# Arduino_extension_connectors.net
KiCad netlist of a schematic drawn in Altium Designer
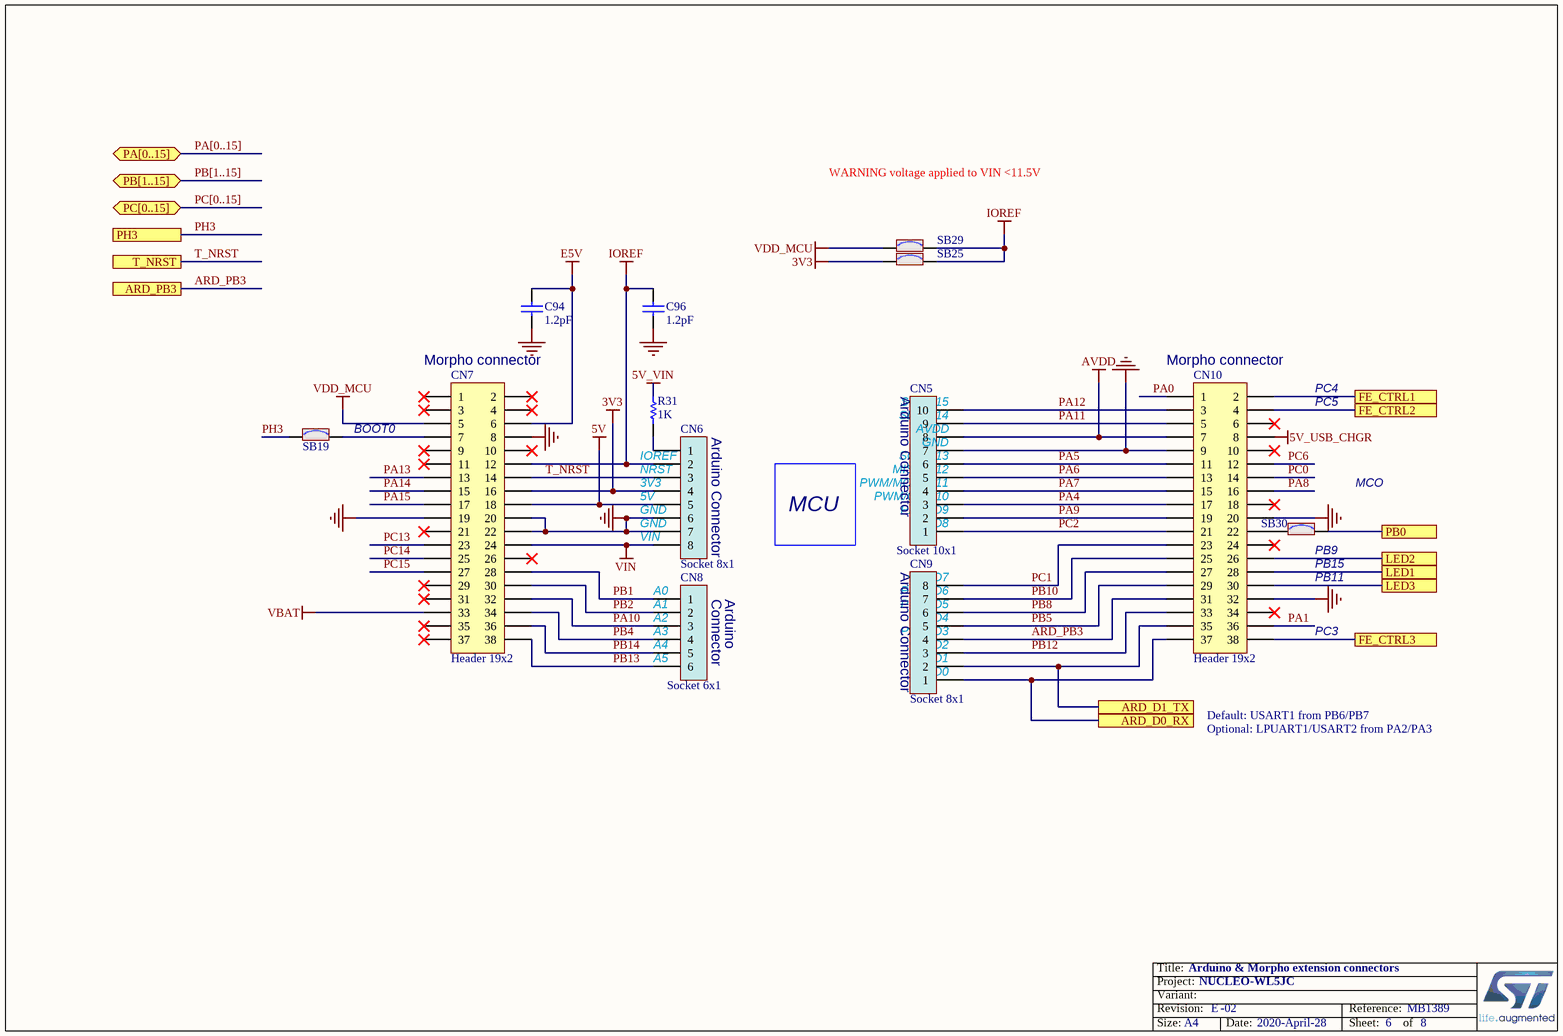
[diagram p0: Arduino_extension_connectors.SchDoc]

(export (version "E")
  (design (tool "Eeschema 10.0.6"))
  (components
    (comp (ref "C94")
      (value "1.2pF")
      (footprint "C0402")
      (description "Capacitor, High Q type for high frequency and high power, SMD, 1.2pF, 50V, 0,05pf, 0402")
      (fields (field (name "INTERNAL_PART_NUMBER") "MCD-02065") (field (name "MANUFACTURER") "MURATA"))
      (libsource (lib "MCD_PARTS_database") (part "Capacitor"))
    )
    (comp (ref "C96")
      (value "1.2pF")
      (footprint "C0402")
      (description "Capacitor, High Q type for high frequency and high power, SMD, 1.2pF, 50V, 0,05pf, 0402")
      (fields (field (name "INTERNAL_PART_NUMBER") "MCD-02065") (field (name "MANUFACTURER") "MURATA"))
      (libsource (lib "MCD_PARTS_database") (part "Capacitor"))
    )
    (comp (ref "CN5")
      (value "Socket 10x1")
      (footprint "CON_SAMTEC_SSW-110-03-X-S")
      (description "Socket, 10x1, 2.54mm, VR, TH, Height 8.51mm/10mm")
      (fields
        (field (name "INTERNAL_PART_NUMBER") "MCD-00262")
        (field (name "MANUFACTURER_PART_NUMBER") "SSW-110-03-x-S")
        (field (name "PROVIDED_BY") "SUBCO")
      )
      (libsource (lib "MCD_PARTS_database") (part "Socket 10x1"))
    )
    (comp (ref "CN6")
      (value "Socket 8x1")
      (footprint "CON_SAMTEC_SSW-108-03-X-S")
      (description "Socket, 8x1, 2.54mm, VR, TH, Height 8.51mm/10mm")
      (fields
        (field (name "INTERNAL_PART_NUMBER") "MCD-00261")
        (field (name "MANUFACTURER_PART_NUMBER") "SSW-108-03-x-S")
        (field (name "PROVIDED_BY") "SUBCO")
      )
      (libsource (lib "MCD_PARTS_database") (part "Socket 8x1"))
    )
    (comp (ref "CN7")
      (value "Header 19x2")
      (footprint "CON_SAMTEC_TSW-119-09-X-D")
      (description "Header, 19x2, 2,54mm, VR, TH, Height 5.84mm/10.16mm")
      (fields
        (field (name "INTERNAL_PART_NUMBER") "MCD-00213")
        (field (name "MANUFACTURER_PART_NUMBER") "TSW-119-09-x-D")
        (field (name "PROVIDED_BY") "SUBCO")
      )
      (libsource (lib "MCD_PARTS_database") (part "Header 19x2"))
    )
    (comp (ref "CN8")
      (value "Socket 6x1")
      (footprint "CON_SAMTEC_SSW-106-03-X-S")
      (description "Socket, 6x1, 2.54mm, VR, TH, Height 8.51mm/10mm")
      (fields
        (field (name "INTERNAL_PART_NUMBER") "MCD-00260")
        (field (name "MANUFACTURER_PART_NUMBER") "SSW-106-03-x-S")
        (field (name "PROVIDED_BY") "SUBCO")
      )
      (libsource (lib "MCD_PARTS_database") (part "Socket 6x1"))
    )
    (comp (ref "CN9")
      (value "Socket 8x1")
      (footprint "CON_SAMTEC_SSW-108-03-X-S")
      (description "Socket, 8x1, 2.54mm, VR, TH, Height 8.51mm/10mm")
      (fields
        (field (name "INTERNAL_PART_NUMBER") "MCD-00261")
        (field (name "MANUFACTURER_PART_NUMBER") "SSW-108-03-x-S")
        (field (name "PROVIDED_BY") "SUBCO")
      )
      (libsource (lib "") (part "Socket 8x1_1"))
    )
    (comp (ref "CN10")
      (value "Header 19x2")
      (footprint "CON_SAMTEC_TSW-119-09-X-D")
      (description "Header, 19x2, 2,54mm, VR, TH, Height 5.84mm/10.16mm")
      (fields
        (field (name "INTERNAL_PART_NUMBER") "MCD-00213")
        (field (name "MANUFACTURER_PART_NUMBER") "TSW-119-09-x-D")
        (field (name "PROVIDED_BY") "SUBCO")
      )
      (libsource (lib "MCD_PARTS_database") (part "Header 19x2"))
    )
    (comp (ref "R31")
      (value "1K")
      (footprint "R0603")
      (description "Resistor,1K,0603,1%,1/10W")
      (fields
        (field (name "INTERNAL_PART_NUMBER") "MCD-00070")
        (field (name "MANUFACTURER_PART_NUMBER") "RC0603FR-071KL")
        (field (name "PROVIDED_BY") "SUBCO")
      )
      (libsource (lib "MCD_PARTS_database") (part "Resistor"))
    )
    (comp (ref "SB19")
      (value "~")
      (footprint "SOLDER-BRIDGE_R0603-0R")
      (description "Solder Bridge ON")
      (fields
        (field (name "INTERNAL_PART_NUMBER") "MCD-00071")
        (field (name "MANUFACTURER_PART_NUMBER") "RC0603JR-070RL")
        (field (name "PROVIDED_BY") "SUBCO")
      )
      (libsource (lib "MCD_PARTS_database") (part "SB_ON"))
    )
    (comp (ref "SB25")
      (value "~")
      (footprint "SOLDER-BRIDGE_R0603-0R")
      (description "Solder Bridge ON")
      (fields
        (field (name "INTERNAL_PART_NUMBER") "MCD-00071")
        (field (name "MANUFACTURER_PART_NUMBER") "RC0603JR-070RL")
        (field (name "PROVIDED_BY") "SUBCO")
      )
      (libsource (lib "MCD_PARTS_database") (part "SB_ON"))
    )
    (comp (ref "SB29")
      (value "~")
      (footprint "SOLDER-BRIDGE_R0603-0R")
      (description "Solder Bridge ON")
      (fields
        (field (name "INTERNAL_PART_NUMBER") "MCD-00071")
        (field (name "MANUFACTURER_PART_NUMBER") "RC0603JR-070RL")
        (field (name "PROVIDED_BY") "SUBCO")
      )
      (libsource (lib "MCD_PARTS_database") (part "SB_ON"))
    )
    (comp (ref "SB30")
      (value "~")
      (footprint "SOLDER-BRIDGE_R0603-0R")
      (description "Solder Bridge ON")
      (fields
        (field (name "INTERNAL_PART_NUMBER") "MCD-00071")
        (field (name "MANUFACTURER_PART_NUMBER") "RC0603JR-070RL")
        (field (name "PROVIDED_BY") "SUBCO")
      )
      (libsource (lib "MCD_PARTS_database") (part "SB_ON"))
    )
  )
  (nets
    (net (code "18") (name "/ARD_D0_RX") (class "Default")
      (node (ref "CN10") (pin "37") (pinfunction "37_37") (pintype "passive"))
      (node (ref "CN9") (pin "1") (pinfunction "1_1") (pintype "passive"))
    )
    (net (code "19") (name "/ARD_D1_TX") (class "Default")
      (node (ref "CN10") (pin "35") (pinfunction "35_35") (pintype "passive"))
      (node (ref "CN9") (pin "2") (pinfunction "2_2") (pintype "passive"))
    )
    (net (code "20") (name "/ARD_PB3") (class "Default")
      (node (ref "CN10") (pin "31") (pinfunction "31_31") (pintype "passive"))
      (node (ref "CN9") (pin "4") (pinfunction "4_4") (pintype "passive"))
    )
    (net (code "21") (name "/FE_CTRL1") (class "Default")
      (node (ref "CN10") (pin "2") (pinfunction "2_2") (pintype "passive"))
    )
    (net (code "22") (name "/FE_CTRL2") (class "Default")
      (node (ref "CN10") (pin "4") (pinfunction "4_4") (pintype "passive"))
    )
    (net (code "23") (name "/FE_CTRL3") (class "Default")
      (node (ref "CN10") (pin "38") (pinfunction "38_38") (pintype "passive"))
    )
    (net (code "24") (name "/LED1") (class "Default")
      (node (ref "CN10") (pin "28") (pinfunction "28_28") (pintype "passive"))
    )
    (net (code "25") (name "/LED2") (class "Default")
      (node (ref "CN10") (pin "26") (pinfunction "26_26") (pintype "passive"))
    )
    (net (code "26") (name "/LED3") (class "Default")
      (node (ref "CN10") (pin "30") (pinfunction "30_30") (pintype "passive"))
    )
    (net (code "27") (name "/PA0") (class "Default")
      (node (ref "CN10") (pin "1") (pinfunction "1_1") (pintype "passive"))
    )
    (net (code "28") (name "/PA1") (class "Default")
      (node (ref "CN10") (pin "36") (pinfunction "36_36") (pintype "passive"))
    )
    (net (code "29") (name "/PA4") (class "Default")
      (node (ref "CN10") (pin "17") (pinfunction "17_17") (pintype "passive"))
      (node (ref "CN5") (pin "3") (pinfunction "3_3") (pintype "passive"))
    )
    (net (code "30") (name "/PA5") (class "Default")
      (node (ref "CN10") (pin "11") (pinfunction "11_11") (pintype "passive"))
      (node (ref "CN5") (pin "6") (pinfunction "6_6") (pintype "passive"))
    )
    (net (code "31") (name "/PA6") (class "Default")
      (node (ref "CN10") (pin "13") (pinfunction "13_13") (pintype "passive"))
      (node (ref "CN5") (pin "5") (pinfunction "5_5") (pintype "passive"))
    )
    (net (code "32") (name "/PA7") (class "Default")
      (node (ref "CN10") (pin "15") (pinfunction "15_15") (pintype "passive"))
      (node (ref "CN5") (pin "4") (pinfunction "4_4") (pintype "passive"))
    )
    (net (code "33") (name "/PA8") (class "Default")
      (node (ref "CN10") (pin "16") (pinfunction "16_16") (pintype "passive"))
    )
    (net (code "34") (name "/PA9") (class "Default")
      (node (ref "CN10") (pin "19") (pinfunction "19_19") (pintype "passive"))
      (node (ref "CN5") (pin "2") (pinfunction "2_2") (pintype "passive"))
    )
    (net (code "35") (name "/PA10") (class "Default")
      (node (ref "CN7") (pin "32") (pinfunction "32_32") (pintype "passive"))
      (node (ref "CN8") (pin "3") (pinfunction "3_3") (pintype "passive"))
    )
    (net (code "36") (name "/PA11") (class "Default")
      (node (ref "CN10") (pin "5") (pinfunction "5_5") (pintype "passive"))
      (node (ref "CN5") (pin "9") (pinfunction "9_9") (pintype "passive"))
    )
    (net (code "37") (name "/PA12") (class "Default")
      (node (ref "CN10") (pin "3") (pinfunction "3_3") (pintype "passive"))
      (node (ref "CN5") (pin "10") (pinfunction "10_10") (pintype "passive"))
    )
    (net (code "38") (name "/PA13") (class "Default")
      (node (ref "CN7") (pin "13") (pinfunction "13_13") (pintype "passive"))
    )
    (net (code "39") (name "/PA14") (class "Default")
      (node (ref "CN7") (pin "15") (pinfunction "15_15") (pintype "passive"))
    )
    (net (code "40") (name "/PA15") (class "Default")
      (node (ref "CN7") (pin "17") (pinfunction "17_17") (pintype "passive"))
    )
    (net (code "42") (name "/PB0") (class "Default")
      (node (ref "SB30") (pin "2") (pinfunction "2_2") (pintype "passive"))
    )
    (net (code "43") (name "/PB1") (class "Default")
      (node (ref "CN7") (pin "28") (pinfunction "28_28") (pintype "passive"))
      (node (ref "CN8") (pin "1") (pinfunction "1_1") (pintype "passive"))
    )
    (net (code "44") (name "/PB2") (class "Default")
      (node (ref "CN7") (pin "30") (pinfunction "30_30") (pintype "passive"))
      (node (ref "CN8") (pin "2") (pinfunction "2_2") (pintype "passive"))
    )
    (net (code "45") (name "/PB4") (class "Default")
      (node (ref "CN7") (pin "34") (pinfunction "34_34") (pintype "passive"))
      (node (ref "CN8") (pin "4") (pinfunction "4_4") (pintype "passive"))
    )
    (net (code "46") (name "/PB5") (class "Default")
      (node (ref "CN10") (pin "29") (pinfunction "29_29") (pintype "passive"))
      (node (ref "CN9") (pin "5") (pinfunction "5_5") (pintype "passive"))
    )
    (net (code "47") (name "/PB8") (class "Default")
      (node (ref "CN10") (pin "27") (pinfunction "27_27") (pintype "passive"))
      (node (ref "CN9") (pin "6") (pinfunction "6_6") (pintype "passive"))
    )
    (net (code "48") (name "/PB10") (class "Default")
      (node (ref "CN10") (pin "25") (pinfunction "25_25") (pintype "passive"))
      (node (ref "CN9") (pin "7") (pinfunction "7_7") (pintype "passive"))
    )
    (net (code "49") (name "/PB12") (class "Default")
      (node (ref "CN10") (pin "33") (pinfunction "33_33") (pintype "passive"))
      (node (ref "CN9") (pin "3") (pinfunction "3_3") (pintype "passive"))
    )
    (net (code "50") (name "/PB13") (class "Default")
      (node (ref "CN7") (pin "38") (pinfunction "38_38") (pintype "passive"))
      (node (ref "CN8") (pin "6") (pinfunction "6_6") (pintype "passive"))
    )
    (net (code "51") (name "/PB14") (class "Default")
      (node (ref "CN7") (pin "36") (pinfunction "36_36") (pintype "passive"))
      (node (ref "CN8") (pin "5") (pinfunction "5_5") (pintype "passive"))
    )
    (net (code "53") (name "/PC0") (class "Default")
      (node (ref "CN10") (pin "14") (pinfunction "14_14") (pintype "passive"))
    )
    (net (code "54") (name "/PC1") (class "Default")
      (node (ref "CN10") (pin "23") (pinfunction "23_23") (pintype "passive"))
      (node (ref "CN9") (pin "8") (pinfunction "8_8") (pintype "passive"))
    )
    (net (code "55") (name "/PC2") (class "Default")
      (node (ref "CN10") (pin "21") (pinfunction "21_21") (pintype "passive"))
      (node (ref "CN5") (pin "1") (pinfunction "1_1") (pintype "passive"))
    )
    (net (code "56") (name "/PC6") (class "Default")
      (node (ref "CN10") (pin "12") (pinfunction "12_12") (pintype "passive"))
    )
    (net (code "57") (name "/PC13") (class "Default")
      (node (ref "CN7") (pin "23") (pinfunction "23_23") (pintype "passive"))
    )
    (net (code "58") (name "/PC14") (class "Default")
      (node (ref "CN7") (pin "25") (pinfunction "25_25") (pintype "passive"))
    )
    (net (code "59") (name "/PC15") (class "Default")
      (node (ref "CN7") (pin "27") (pinfunction "27_27") (pintype "passive"))
    )
    (net (code "61") (name "/PH3") (class "Default")
      (node (ref "SB19") (pin "1") (pinfunction "1_1") (pintype "passive"))
    )
    (net (code "62") (name "/T_NRST") (class "Default")
      (node (ref "CN6") (pin "3") (pinfunction "3_3") (pintype "passive"))
      (node (ref "CN7") (pin "14") (pinfunction "14_14") (pintype "passive"))
    )
    (net (code "63") (name "3V3") (class "Default")
      (node (ref "CN6") (pin "4") (pinfunction "4_4") (pintype "passive"))
      (node (ref "CN7") (pin "16") (pinfunction "16_16") (pintype "passive"))
      (node (ref "SB25") (pin "1") (pinfunction "1_1") (pintype "passive"))
    )
    (net (code "64") (name "5V") (class "Default")
      (node (ref "CN6") (pin "5") (pinfunction "5_5") (pintype "passive"))
      (node (ref "CN7") (pin "18") (pinfunction "18_18") (pintype "passive"))
    )
    (net (code "65") (name "5V_USB_CHGR") (class "Default")
      (node (ref "CN10") (pin "8") (pinfunction "8_8") (pintype "passive"))
    )
    (net (code "66") (name "5V_VIN") (class "Default")
      (node (ref "R31") (pin "2") (pinfunction "2_2") (pintype "passive"))
    )
    (net (code "67") (name "AVDD") (class "Default")
      (node (ref "CN10") (pin "7") (pinfunction "7_7") (pintype "passive"))
      (node (ref "CN5") (pin "8") (pinfunction "8_8") (pintype "passive"))
    )
    (net (code "68") (name "E5V") (class "Default")
      (node (ref "C94") (pin "2") (pinfunction "2_2") (pintype "passive"))
      (node (ref "CN7") (pin "6") (pinfunction "6_6") (pintype "passive"))
    )
    (net (code "69") (name "GND") (class "Default")
      (node (ref "C94") (pin "1") (pinfunction "1_1") (pintype "passive"))
      (node (ref "C96") (pin "1") (pinfunction "1_1") (pintype "passive"))
      (node (ref "CN10") (pin "20") (pinfunction "20_20") (pintype "passive"))
      (node (ref "CN10") (pin "32") (pinfunction "32_32") (pintype "passive"))
      (node (ref "CN10") (pin "9") (pinfunction "9_9") (pintype "passive"))
      (node (ref "CN5") (pin "7") (pinfunction "7_7") (pintype "passive"))
      (node (ref "CN6") (pin "6") (pinfunction "6_6") (pintype "passive"))
      (node (ref "CN6") (pin "7") (pinfunction "7_7") (pintype "passive"))
      (node (ref "CN7") (pin "19") (pinfunction "19_19") (pintype "passive"))
      (node (ref "CN7") (pin "20") (pinfunction "20_20") (pintype "passive"))
      (node (ref "CN7") (pin "22") (pinfunction "22_22") (pintype "passive"))
      (node (ref "CN7") (pin "8") (pinfunction "8_8") (pintype "passive"))
    )
    (net (code "70") (name "IOREF") (class "Default")
      (node (ref "C96") (pin "2") (pinfunction "2_2") (pintype "passive"))
      (node (ref "CN6") (pin "2") (pinfunction "2_2") (pintype "passive"))
      (node (ref "CN7") (pin "12") (pinfunction "12_12") (pintype "passive"))
      (node (ref "SB25") (pin "2") (pinfunction "2_2") (pintype "passive"))
      (node (ref "SB29") (pin "2") (pinfunction "2_2") (pintype "passive"))
    )
    (net (code "71") (name "Net-(CN6-Pad1)") (class "Default")
      (node (ref "CN6") (pin "1") (pinfunction "1_1") (pintype "passive"))
      (node (ref "R31") (pin "1") (pinfunction "1_1") (pintype "passive"))
    )
    (net (code "72") (name "Net-(CN7-Pad7)") (class "Default")
      (node (ref "CN7") (pin "7") (pinfunction "7_7") (pintype "passive"))
      (node (ref "SB19") (pin "2") (pinfunction "2_2") (pintype "passive"))
    )
    (net (code "73") (name "Net-(CN10-Pad22)") (class "Default")
      (node (ref "CN10") (pin "22") (pinfunction "22_22") (pintype "passive"))
      (node (ref "SB30") (pin "1") (pinfunction "1_1") (pintype "passive"))
    )
    (net (code "74") (name "VBAT") (class "Default")
      (node (ref "CN7") (pin "33") (pinfunction "33_33") (pintype "passive"))
    )
    (net (code "75") (name "VDD_MCU") (class "Default")
      (node (ref "CN7") (pin "5") (pinfunction "5_5") (pintype "passive"))
      (node (ref "SB29") (pin "1") (pinfunction "1_1") (pintype "passive"))
    )
    (net (code "76") (name "VIN") (class "Default")
      (node (ref "CN6") (pin "8") (pinfunction "8_8") (pintype "passive"))
      (node (ref "CN7") (pin "24") (pinfunction "24_24") (pintype "passive"))
    )
    (net (code "77") (name "unconnected-(CN7-Pad1)") (class "Default")
      (node (ref "CN7") (pin "1") (pinfunction "1_1") (pintype "passive+no_connect"))
    )
    (net (code "78") (name "unconnected-(CN7-Pad2)") (class "Default")
      (node (ref "CN7") (pin "2") (pinfunction "2_2") (pintype "passive+no_connect"))
    )
    (net (code "79") (name "unconnected-(CN7-Pad3)") (class "Default")
      (node (ref "CN7") (pin "3") (pinfunction "3_3") (pintype "passive+no_connect"))
    )
    (net (code "80") (name "unconnected-(CN7-Pad4)") (class "Default")
      (node (ref "CN7") (pin "4") (pinfunction "4_4") (pintype "passive+no_connect"))
    )
    (net (code "81") (name "unconnected-(CN7-Pad9)") (class "Default")
      (node (ref "CN7") (pin "9") (pinfunction "9_9") (pintype "passive+no_connect"))
    )
    (net (code "82") (name "unconnected-(CN7-Pad10)") (class "Default")
      (node (ref "CN7") (pin "10") (pinfunction "10_10") (pintype "passive+no_connect"))
    )
    (net (code "83") (name "unconnected-(CN7-Pad11)") (class "Default")
      (node (ref "CN7") (pin "11") (pinfunction "11_11") (pintype "passive+no_connect"))
    )
    (net (code "84") (name "unconnected-(CN7-Pad21)") (class "Default")
      (node (ref "CN7") (pin "21") (pinfunction "21_21") (pintype "passive+no_connect"))
    )
    (net (code "85") (name "unconnected-(CN7-Pad26)") (class "Default")
      (node (ref "CN7") (pin "26") (pinfunction "26_26") (pintype "passive+no_connect"))
    )
    (net (code "86") (name "unconnected-(CN7-Pad29)") (class "Default")
      (node (ref "CN7") (pin "29") (pinfunction "29_29") (pintype "passive+no_connect"))
    )
    (net (code "87") (name "unconnected-(CN7-Pad31)") (class "Default")
      (node (ref "CN7") (pin "31") (pinfunction "31_31") (pintype "passive+no_connect"))
    )
    (net (code "88") (name "unconnected-(CN7-Pad35)") (class "Default")
      (node (ref "CN7") (pin "35") (pinfunction "35_35") (pintype "passive+no_connect"))
    )
    (net (code "89") (name "unconnected-(CN7-Pad37)") (class "Default")
      (node (ref "CN7") (pin "37") (pinfunction "37_37") (pintype "passive+no_connect"))
    )
    (net (code "90") (name "unconnected-(CN10-Pad6)") (class "Default")
      (node (ref "CN10") (pin "6") (pinfunction "6_6") (pintype "passive+no_connect"))
    )
    (net (code "91") (name "unconnected-(CN10-Pad10)") (class "Default")
      (node (ref "CN10") (pin "10") (pinfunction "10_10") (pintype "passive+no_connect"))
    )
    (net (code "92") (name "unconnected-(CN10-Pad18)") (class "Default")
      (node (ref "CN10") (pin "18") (pinfunction "18_18") (pintype "passive+no_connect"))
    )
    (net (code "93") (name "unconnected-(CN10-Pad24)") (class "Default")
      (node (ref "CN10") (pin "24") (pinfunction "24_24") (pintype "passive+no_connect"))
    )
    (net (code "94") (name "unconnected-(CN10-Pad34)") (class "Default")
      (node (ref "CN10") (pin "34") (pinfunction "34_34") (pintype "passive+no_connect"))
    )
  )
)
